# Sheet1.net
KiCad netlist of a schematic drawn in Altium Designer
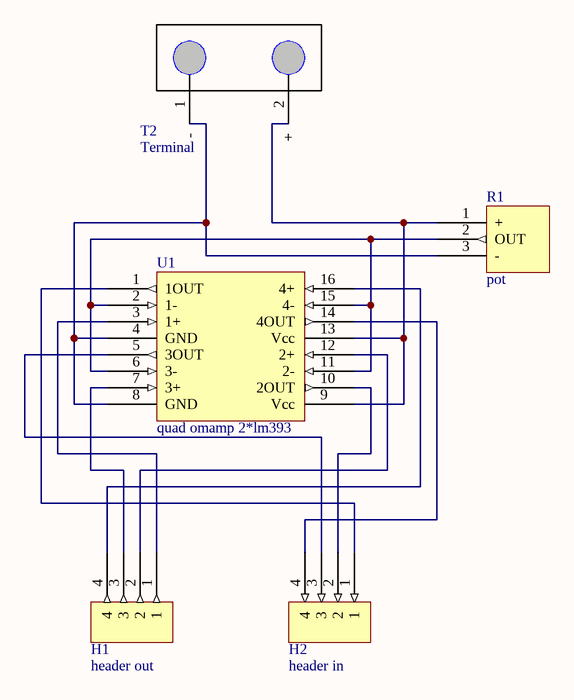
[diagram p0: Sheet1.SchDoc]

(export (version "E")
  (design (tool "Eeschema 10.0.6"))
  (components
    (comp (ref "H1") (value "header out") (footprint "headers") (libsource (lib "parts") (part "header out")))
    (comp (ref "H2") (value "header in") (footprint "headers") (libsource (lib "parts") (part "header in")))
    (comp (ref "R1") (value "pot") (footprint "pot") (libsource (lib "parts") (part "pot")))
    (comp (ref "T2") (value "Terminal") (footprint "Terminal") (libsource (lib "parts") (part "Terminal")))
    (comp (ref "U1")
      (value "quad omamp 2*lm393")
      (footprint "quad omamp 2*lm393")
      (libsource (lib "parts") (part "quad omamp 2*lm393"))
    )
  )
  (nets
    (net (code "1") (name "Net-(R1-+)") (class "Default")
      (node (ref "R1") (pin "1") (pinfunction "+_1") (pintype "passive"))
      (node (ref "U1") (pin "13") (pinfunction "Vcc_13") (pintype "passive"))
      (node (ref "U1") (pin "9") (pinfunction "Vcc_9") (pintype "passive"))
    )
    (net (code "2") (name "Net-(R1--)") (class "Default")
      (node (ref "R1") (pin "3") (pinfunction "-_3") (pintype "passive"))
      (node (ref "U1") (pin "4") (pinfunction "GND_4") (pintype "passive"))
      (node (ref "U1") (pin "8") (pinfunction "GND_8") (pintype "passive"))
    )
    (net (code "3") (name "Net-(R1-OUT)") (class "Default")
      (node (ref "R1") (pin "2") (pinfunction "OUT_2") (pintype "output"))
      (node (ref "U1") (pin "11") (pinfunction "2-_11") (pintype "input"))
      (node (ref "U1") (pin "15") (pinfunction "4-_15") (pintype "input"))
      (node (ref "U1") (pin "2") (pinfunction "1-_2") (pintype "input"))
      (node (ref "U1") (pin "6") (pinfunction "3-_6") (pintype "input"))
    )
    (net (code "4") (name "Net-(U1-1+)") (class "Default")
      (node (ref "H1") (pin "1") (pinfunction "1_1") (pintype "output"))
      (node (ref "U1") (pin "3") (pinfunction "1+_3") (pintype "input"))
    )
    (net (code "5") (name "Net-(U1-1OUT)") (class "Default")
      (node (ref "H2") (pin "1") (pinfunction "1_1") (pintype "input"))
      (node (ref "U1") (pin "1") (pinfunction "1OUT_1") (pintype "output"))
    )
    (net (code "6") (name "Net-(U1-2+)") (class "Default")
      (node (ref "H1") (pin "2") (pinfunction "2_2") (pintype "output"))
      (node (ref "U1") (pin "12") (pinfunction "2+_12") (pintype "input"))
    )
    (net (code "7") (name "Net-(U1-2OUT)") (class "Default")
      (node (ref "H2") (pin "2") (pinfunction "2_2") (pintype "input"))
      (node (ref "U1") (pin "10") (pinfunction "2OUT_10") (pintype "output"))
    )
    (net (code "8") (name "Net-(U1-3+)") (class "Default")
      (node (ref "H1") (pin "3") (pinfunction "3_3") (pintype "output"))
      (node (ref "U1") (pin "7") (pinfunction "3+_7") (pintype "input"))
    )
    (net (code "9") (name "Net-(U1-3OUT)") (class "Default")
      (node (ref "H2") (pin "3") (pinfunction "3_3") (pintype "input"))
      (node (ref "U1") (pin "5") (pinfunction "3OUT_5") (pintype "output"))
    )
    (net (code "10") (name "Net-(U1-4+)") (class "Default")
      (node (ref "H1") (pin "4") (pinfunction "4_4") (pintype "output"))
      (node (ref "U1") (pin "16") (pinfunction "4+_16") (pintype "input"))
    )
    (net (code "11") (name "Net-(U1-4OUT)") (class "Default")
      (node (ref "H2") (pin "4") (pinfunction "4_4") (pintype "input"))
      (node (ref "U1") (pin "14") (pinfunction "4OUT_14") (pintype "output"))
    )
    (net (code "12") (name "unconnected-(T2-+-Pad2)") (class "Default")
      (node (ref "T2") (pin "2") (pinfunction "+_2") (pintype "passive"))
    )
    (net (code "13") (name "unconnected-(T2---Pad1)") (class "Default")
      (node (ref "T2") (pin "1") (pinfunction "-_1") (pintype "passive"))
    )
  )
)
